# rf_lpf_160.net
KiCad netlist of a schematic drawn in Altium Designer
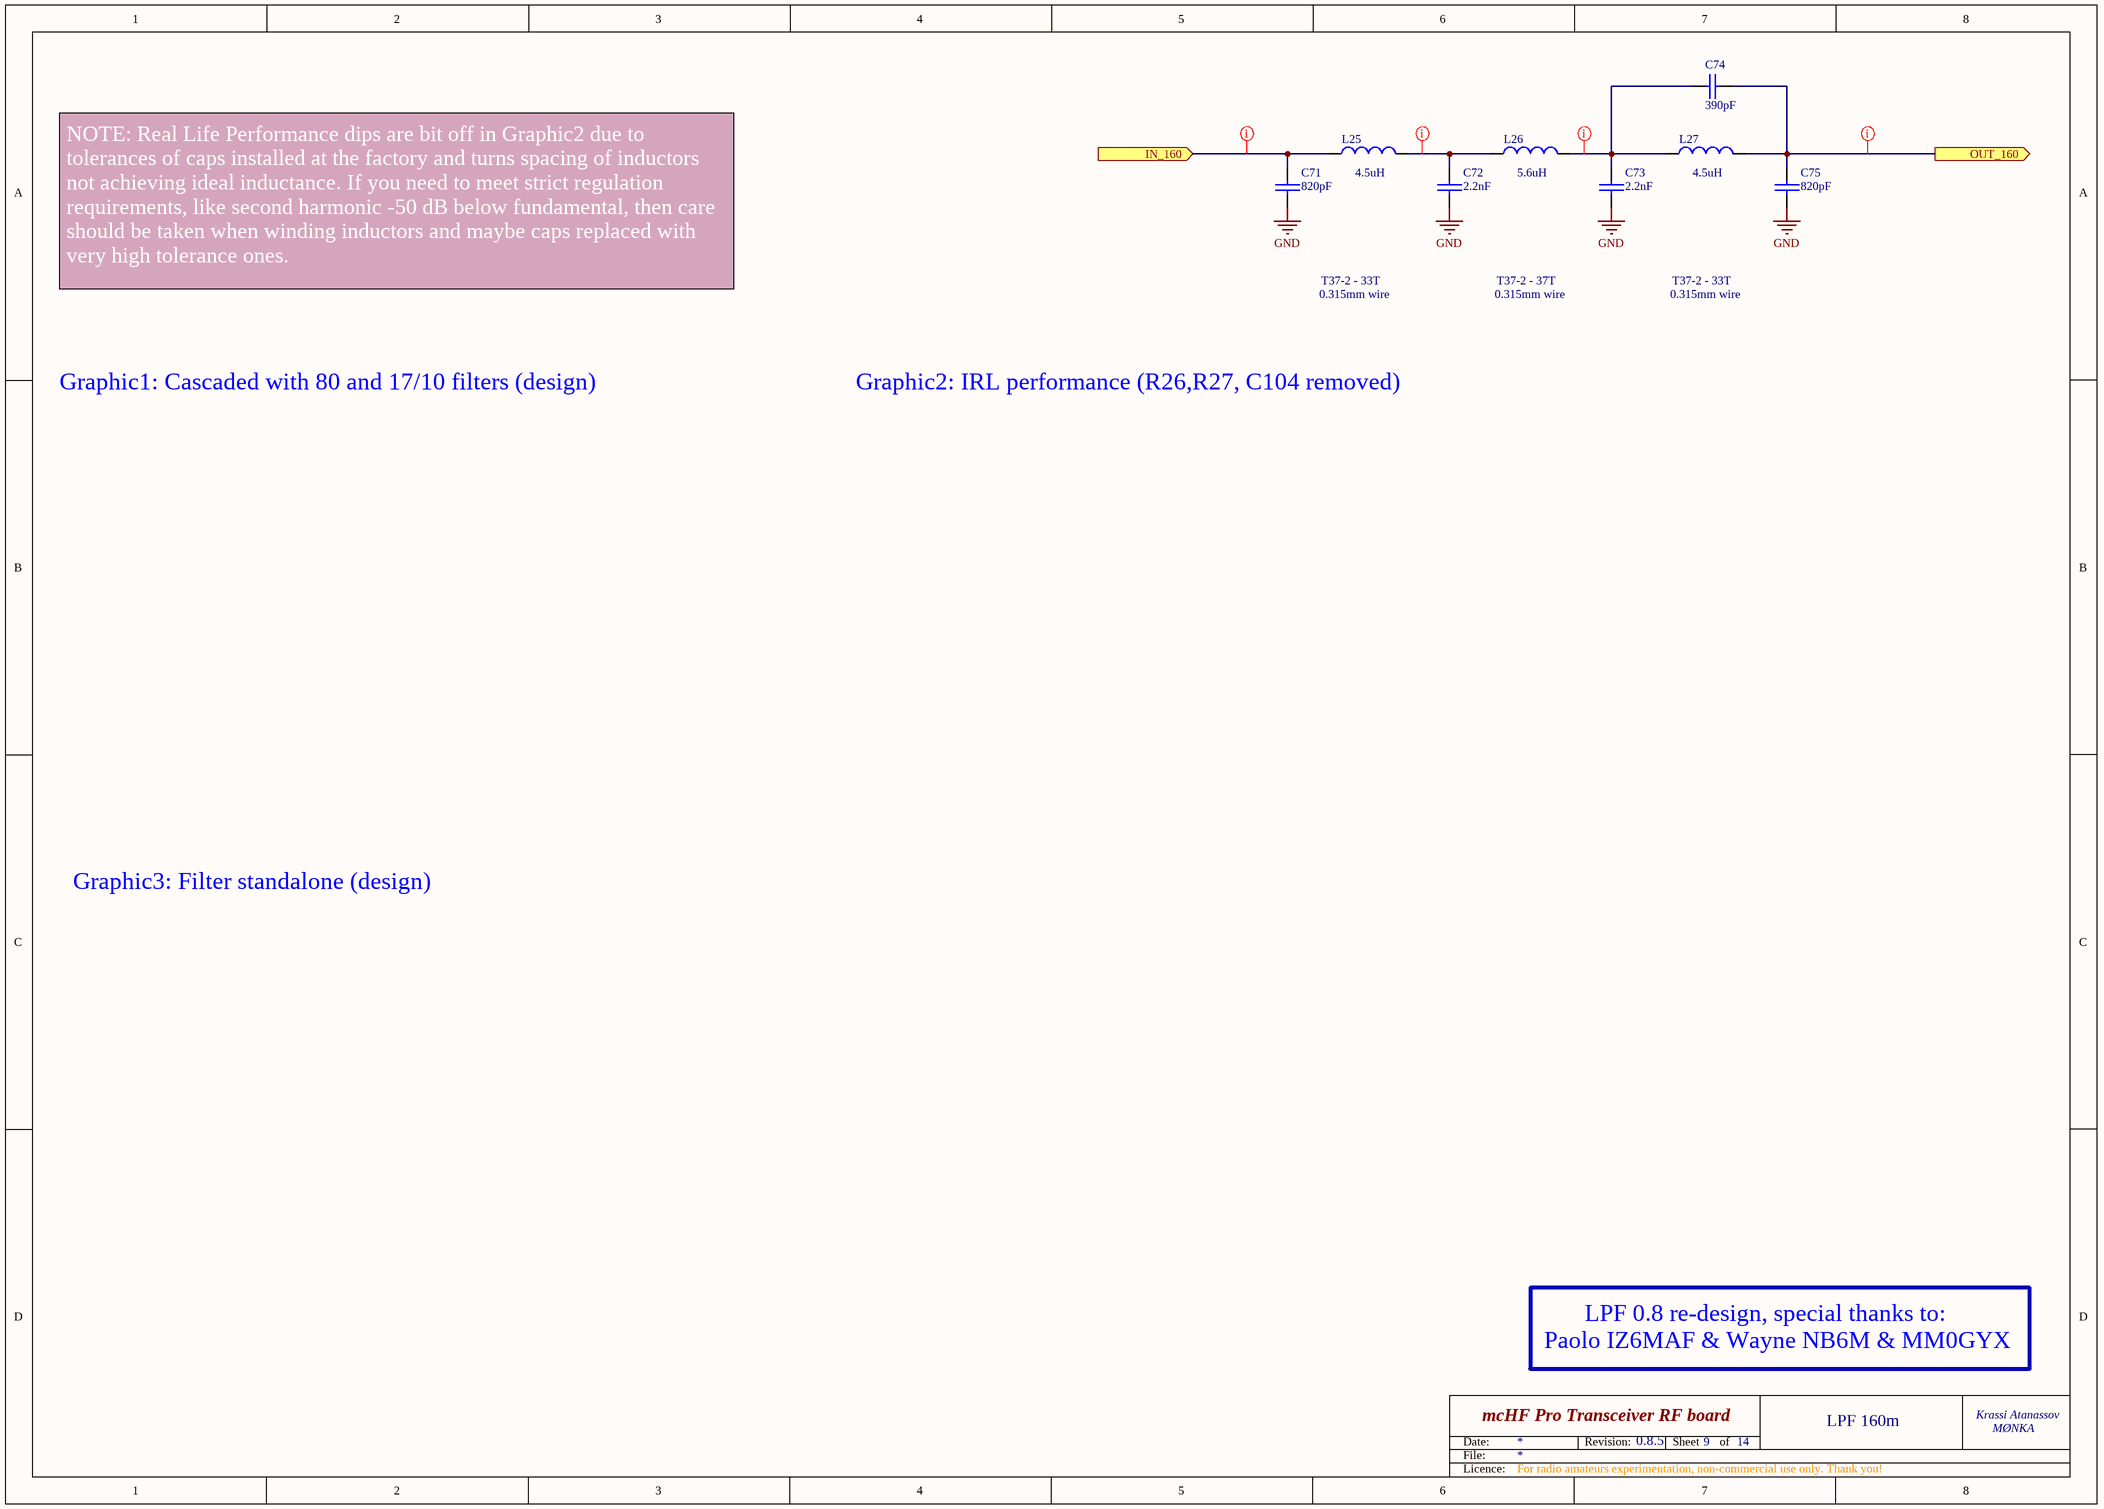
[diagram p0: rf_lpf_160.SchDoc]

(export (version "E")
  (design (tool "Eeschema 10.0.6"))
  (components
    (comp (ref "C71")
      (value "820pF")
      (footprint "0805")
      (description "Capacitor")
      (fields (field (name "VOLTAGE") "100V"))
      (libsource (lib "mcHF_rf") (part "CAP"))
    )
    (comp (ref "C72")
      (value "2.2nF")
      (footprint "0805")
      (description "Capacitor")
      (fields (field (name "VOLTAGE") "100V"))
      (libsource (lib "mcHF_rf") (part "CAP"))
    )
    (comp (ref "C73")
      (value "2.2nF")
      (footprint "0805")
      (description "Capacitor")
      (fields (field (name "VOLTAGE") "100V"))
      (libsource (lib "mcHF_rf") (part "CAP"))
    )
    (comp (ref "C74")
      (value "390pF")
      (footprint "0805")
      (description "Capacitor")
      (fields (field (name "VOLTAGE") "100V"))
      (libsource (lib "mcHF_rf") (part "CAP"))
    )
    (comp (ref "C75")
      (value "820pF")
      (footprint "0805")
      (description "Capacitor")
      (fields (field (name "VOLTAGE") "100V"))
      (libsource (lib "mcHF_rf") (part "CAP"))
    )
    (comp (ref "L25")
      (value "T37-2")
      (footprint "LPF_IND")
      (description "T37-2 handwound inductor")
      (fields (field (name "INDUCTANCE") "4.5uH"))
      (libsource (lib "mcHF_rf") (part "LPF_IND"))
    )
    (comp (ref "L26")
      (value "T37-2")
      (footprint "LPF_IND")
      (description "T37-2 handwound inductor")
      (fields (field (name "INDUCTANCE") "5.6uH"))
      (libsource (lib "mcHF_rf") (part "LPF_IND"))
    )
    (comp (ref "L27")
      (value "T37-2")
      (footprint "LPF_IND")
      (description "T37-2 handwound inductor")
      (fields (field (name "INDUCTANCE") "4.5uH"))
      (libsource (lib "mcHF_rf") (part "LPF_IND"))
    )
  )
  (nets
    (net (code "1") (name "/IN_160") (class "Default")
      (node (ref "C71") (pin "1") (pinfunction "1_1") (pintype "passive"))
      (node (ref "L25") (pin "1") (pinfunction "1_1") (pintype "passive"))
    )
    (net (code "2") (name "/OUT_160") (class "Default")
      (node (ref "C74") (pin "1") (pinfunction "1_1") (pintype "passive"))
      (node (ref "C75") (pin "1") (pinfunction "1_1") (pintype "passive"))
      (node (ref "L27") (pin "2") (pinfunction "2_2") (pintype "passive"))
    )
    (net (code "3") (name "GND") (class "Default")
      (node (ref "C71") (pin "2") (pinfunction "2_2") (pintype "passive"))
      (node (ref "C72") (pin "2") (pinfunction "2_2") (pintype "passive"))
      (node (ref "C73") (pin "2") (pinfunction "2_2") (pintype "passive"))
      (node (ref "C75") (pin "2") (pinfunction "2_2") (pintype "passive"))
    )
    (net (code "4") (name "Net-(C72-Pad1)") (class "Default")
      (node (ref "C72") (pin "1") (pinfunction "1_1") (pintype "passive"))
      (node (ref "L25") (pin "2") (pinfunction "2_2") (pintype "passive"))
      (node (ref "L26") (pin "1") (pinfunction "1_1") (pintype "passive"))
    )
    (net (code "5") (name "Net-(C73-Pad1)") (class "Default")
      (node (ref "C73") (pin "1") (pinfunction "1_1") (pintype "passive"))
      (node (ref "C74") (pin "2") (pinfunction "2_2") (pintype "passive"))
      (node (ref "L26") (pin "2") (pinfunction "2_2") (pintype "passive"))
      (node (ref "L27") (pin "1") (pinfunction "1_1") (pintype "passive"))
    )
  )
)
